# 2025-565-V1.net
KiCad netlist of a schematic drawn in Altium Designer
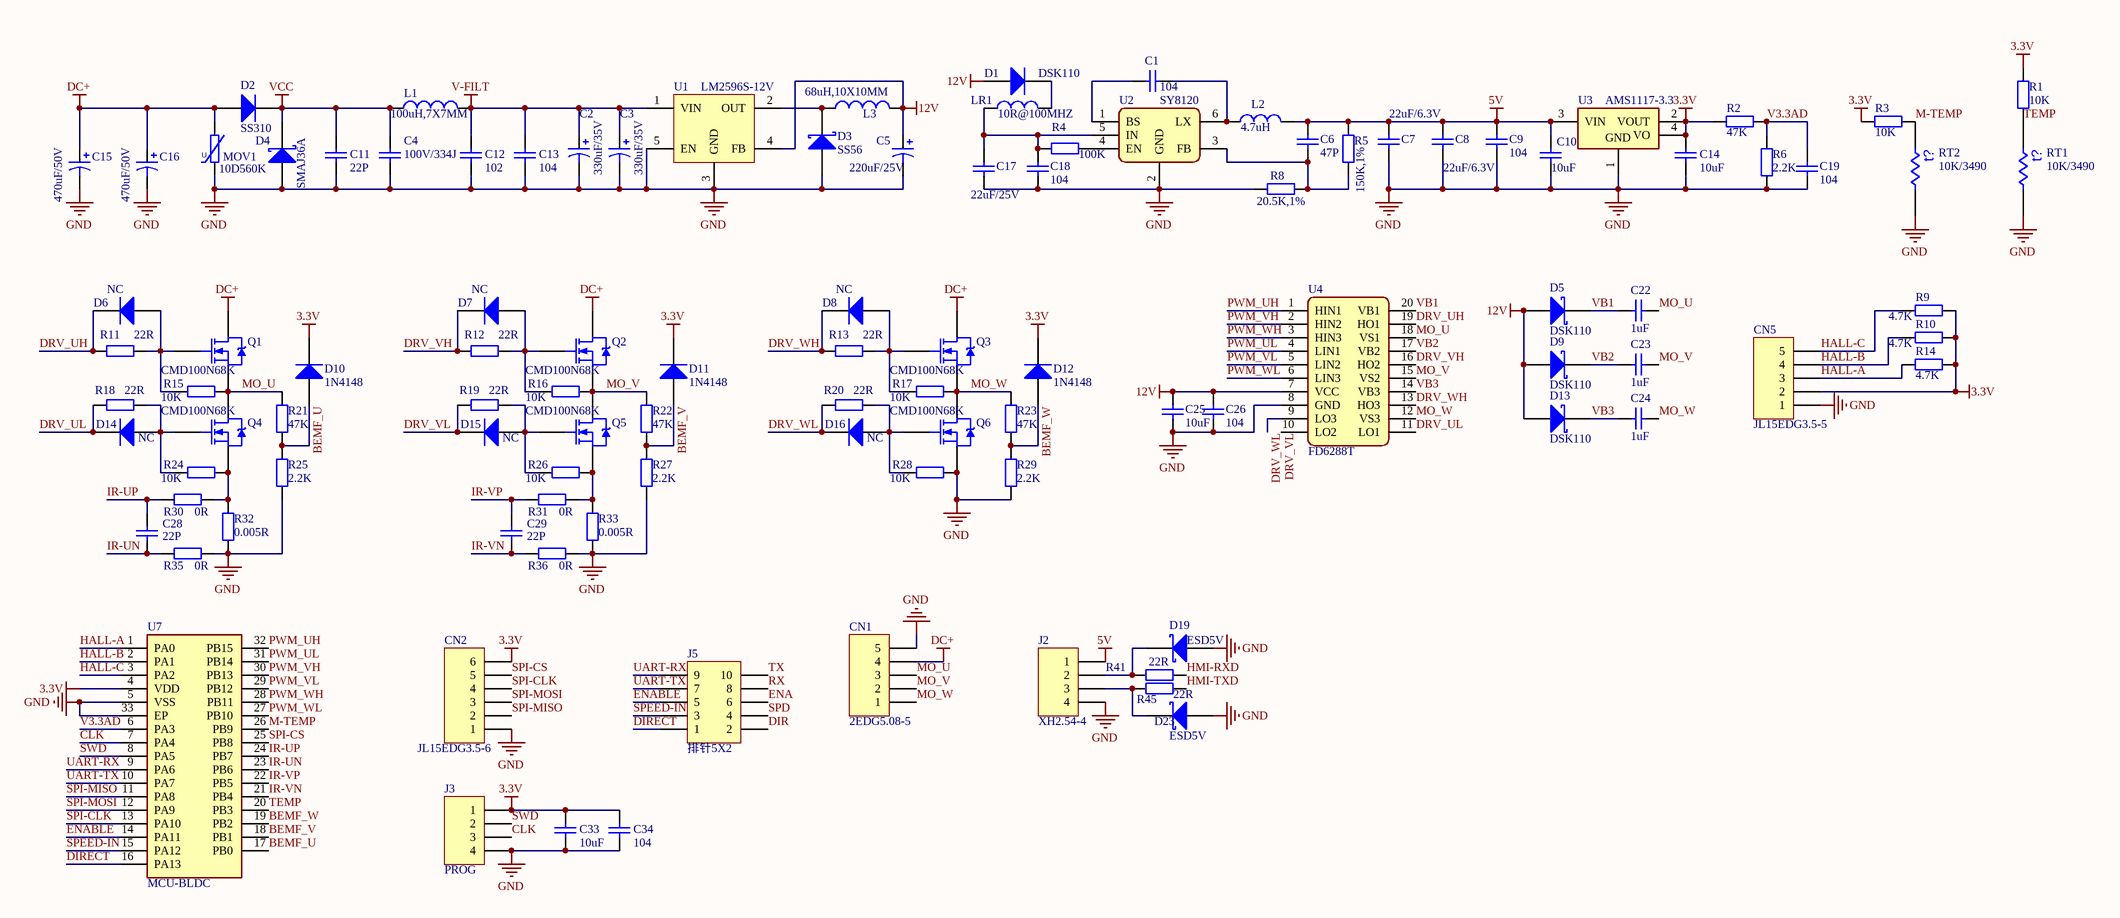
[diagram p0: 2025-565-V1.SchDoc]

(export (version "E")
  (design (tool "Eeschema 10.0.6"))
  (components
    (comp (ref "C1")
      (value "104")
      (footprint "0603-C")
      (description "0603电容")
      (fields (field (name "PUBLISHER") "Altium Limited"))
      (libsource (lib "Miscellaneous Devices") (part "Cap"))
    )
    (comp (ref "C2")
      (value "330uF/35V")
      (footprint "EC10-V5")
      (description "插件电解电容")
      (fields (field (name "PUBLISHER") "Altium Limited"))
      (libsource (lib "Miscellaneous Devices") (part "Cap Pol1"))
    )
    (comp (ref "C3")
      (value "330uF/35V")
      (footprint "EC10-V5")
      (description "插件电解电容")
      (fields (field (name "PUBLISHER") "Altium Limited"))
      (libsource (lib "Miscellaneous Devices") (part "Cap Pol1"))
    )
    (comp (ref "C4")
      (value "100V/334J")
      (footprint "CAP5-7.2X7.5X3.5")
      (description "校正电容")
      (fields (field (name "PUBLISHER") "Altium Limited"))
      (libsource (lib "Miscellaneous Devices") (part "Cap"))
    )
    (comp (ref "C5")
      (value "220uF/25V")
      (footprint "CAP_63*77")
      (description "贴片电解电容")
      (fields (field (name "PUBLISHER") "Altium Limited"))
      (libsource (lib "Miscellaneous Devices") (part "Cap Pol1"))
    )
    (comp (ref "C6")
      (value "47P")
      (footprint "0603-C")
      (description "0603电容")
      (fields (field (name "PUBLISHER") "Altium Limited"))
      (libsource (lib "Miscellaneous Devices") (part "Cap"))
    )
    (comp (ref "C7")
      (value "22uF/6.3V")
      (footprint "0603-C")
      (description "0603电容")
      (fields (field (name "PUBLISHER") "Altium Limited"))
      (libsource (lib "Miscellaneous Devices") (part "Cap"))
    )
    (comp (ref "C8")
      (value "22uF/6.3V")
      (footprint "0603-C")
      (description "0603电容")
      (fields (field (name "PUBLISHER") "Altium Limited"))
      (libsource (lib "Miscellaneous Devices") (part "Cap"))
    )
    (comp (ref "C9")
      (value "104")
      (footprint "0603-C")
      (description "0603电容")
      (fields (field (name "PUBLISHER") "Altium Limited"))
      (libsource (lib "Miscellaneous Devices") (part "Cap"))
    )
    (comp (ref "C10")
      (value "10uF")
      (footprint "0603-C")
      (description "0603电容")
      (fields (field (name "PUBLISHER") "Altium Limited"))
      (libsource (lib "Miscellaneous Devices") (part "Cap"))
    )
    (comp (ref "C11")
      (value "22P")
      (footprint "0603-C")
      (description "0603电容")
      (fields (field (name "PUBLISHER") "Altium Limited"))
      (libsource (lib "Miscellaneous Devices") (part "Cap"))
    )
    (comp (ref "C12")
      (value "102")
      (footprint "0603-C")
      (description "0603电容")
      (fields (field (name "PUBLISHER") "Altium Limited"))
      (libsource (lib "Miscellaneous Devices") (part "Cap"))
    )
    (comp (ref "C13")
      (value "104")
      (footprint "0603-C")
      (description "0603电容")
      (fields (field (name "PUBLISHER") "Altium Limited"))
      (libsource (lib "Miscellaneous Devices") (part "Cap"))
    )
    (comp (ref "C14")
      (value "10uF")
      (footprint "0603-C")
      (description "0603电容")
      (fields (field (name "PUBLISHER") "Altium Limited"))
      (libsource (lib "Miscellaneous Devices") (part "Cap"))
    )
    (comp (ref "C15")
      (value "470uF/50V")
      (footprint "EC10-V5")
      (description "插件电解电容")
      (fields (field (name "PUBLISHER") "Altium Limited"))
      (libsource (lib "Miscellaneous Devices") (part "Cap Pol1"))
    )
    (comp (ref "C16")
      (value "470uF/50V")
      (footprint "EC10-V5")
      (description "插件电解电容")
      (fields (field (name "PUBLISHER") "Altium Limited"))
      (libsource (lib "Miscellaneous Devices") (part "Cap Pol1"))
    )
    (comp (ref "C17")
      (value "22uF/25V")
      (footprint "1206-C")
      (description "1206电容")
      (fields (field (name "PUBLISHER") "Altium Limited"))
      (libsource (lib "Miscellaneous Devices") (part "Cap"))
    )
    (comp (ref "C18")
      (value "104")
      (footprint "0603-C")
      (description "0603电容")
      (fields (field (name "PUBLISHER") "Altium Limited"))
      (libsource (lib "Miscellaneous Devices") (part "Cap"))
    )
    (comp (ref "C19")
      (value "104")
      (footprint "0603-C")
      (description "0603电容")
      (fields (field (name "PUBLISHER") "Altium Limited"))
      (libsource (lib "Miscellaneous Devices") (part "Cap"))
    )
    (comp (ref "C22")
      (value "1uF")
      (footprint "0603-C")
      (description "0603电容")
      (fields (field (name "PUBLISHER") "Altium Limited"))
      (libsource (lib "Miscellaneous Devices") (part "Cap"))
    )
    (comp (ref "C23")
      (value "1uF")
      (footprint "0603-C")
      (description "0603电容")
      (fields (field (name "PUBLISHER") "Altium Limited"))
      (libsource (lib "Miscellaneous Devices") (part "Cap"))
    )
    (comp (ref "C24")
      (value "1uF")
      (footprint "0603-C")
      (description "0603电容")
      (fields (field (name "PUBLISHER") "Altium Limited"))
      (libsource (lib "Miscellaneous Devices") (part "Cap"))
    )
    (comp (ref "C25")
      (value "10uF")
      (footprint "1206-R")
      (description "1206电容")
      (fields (field (name "PUBLISHER") "Altium Limited"))
      (libsource (lib "Miscellaneous Devices") (part "Cap"))
    )
    (comp (ref "C26")
      (value "104")
      (footprint "0603-C")
      (description "0603电容")
      (fields (field (name "PUBLISHER") "Altium Limited"))
      (libsource (lib "Miscellaneous Devices") (part "Cap"))
    )
    (comp (ref "C28")
      (value "22P")
      (footprint "0603-C")
      (description "0603电容")
      (fields (field (name "PUBLISHER") "Altium Limited"))
      (libsource (lib "Miscellaneous Devices") (part "Cap"))
    )
    (comp (ref "C29")
      (value "22P")
      (footprint "0603-C")
      (description "0603电容")
      (fields (field (name "PUBLISHER") "Altium Limited"))
      (libsource (lib "Miscellaneous Devices") (part "Cap"))
    )
    (comp (ref "C33")
      (value "10uF")
      (footprint "0603-C")
      (description "0603电容")
      (fields (field (name "PUBLISHER") "Altium Limited"))
      (libsource (lib "Miscellaneous Devices") (part "Cap"))
    )
    (comp (ref "C34")
      (value "104")
      (footprint "0603-C")
      (description "0603电容")
      (fields (field (name "PUBLISHER") "Altium Limited"))
      (libsource (lib "Miscellaneous Devices") (part "Cap"))
    )
    (comp (ref "CN1")
      (value "2EDG5.08-5")
      (footprint "CON5_5.08MM_2EDG")
      (description "插拔端子")
      (fields (field (name "PUBLISHER") "Altium Limited"))
      (libsource (lib "Miscellaneous Connectors") (part "Header 5"))
    )
    (comp (ref "CN2")
      (value "JL15EDG3.5-6")
      (footprint "CON3.5*6-H-SPEC")
      (description "插拔端子")
      (fields (field (name "PUBLISHER") "Altium Limited"))
      (libsource (lib "Miscellaneous Connectors") (part "Header 6"))
    )
    (comp (ref "CN5")
      (value "JL15EDG3.5-5")
      (footprint "CON3.5*5-H-SPEC")
      (description "插拔端子")
      (fields (field (name "PUBLISHER") "Altium Limited"))
      (libsource (lib "Miscellaneous Connectors") (part "Header 5"))
    )
    (comp (ref "D1")
      (value "DSK110")
      (footprint "SOD-123FL")
      (description "二极管")
      (fields (field (name "PUBLISHER") "Altium Limited"))
      (libsource (lib "Miscellaneous Devices") (part "Diode"))
    )
    (comp (ref "D2")
      (value "SS310")
      (footprint "SMA-DO-214AC")
      (description "二极管")
      (fields (field (name "PUBLISHER") "Altium Limited"))
      (libsource (lib "Miscellaneous Devices") (part "Diode"))
    )
    (comp (ref "D3")
      (value "SS56")
      (footprint "SMB_DO-214AA")
      (description "肖特基二极管")
      (fields (field (name "PUBLISHER") "Altium Limited"))
      (libsource (lib "Miscellaneous Devices") (part "D Schottky"))
    )
    (comp (ref "D4")
      (value "SMAJ36A")
      (footprint "SMA-DO-214AC")
      (description "TVS二极管")
      (fields (field (name "PUBLISHER") "Altium Limited"))
      (libsource (lib "Miscellaneous Devices") (part "D Schottky"))
    )
    (comp (ref "D5")
      (value "DSK110")
      (footprint "SOD-123FL")
      (description "肖特基二极管")
      (fields (field (name "PUBLISHER") "Altium Limited"))
      (libsource (lib "Miscellaneous Devices") (part "D Schottky"))
    )
    (comp (ref "D6")
      (value "NC")
      (footprint "SOD-123")
      (description "Default Diode")
      (fields (field (name "PUBLISHER") "Altium Limited"))
      (libsource (lib "Miscellaneous Devices") (part "Diode"))
    )
    (comp (ref "D7")
      (value "NC")
      (footprint "SOD-123")
      (description "Default Diode")
      (fields (field (name "PUBLISHER") "Altium Limited"))
      (libsource (lib "Miscellaneous Devices") (part "Diode"))
    )
    (comp (ref "D8")
      (value "NC")
      (footprint "SOD-123")
      (description "Default Diode")
      (fields (field (name "PUBLISHER") "Altium Limited"))
      (libsource (lib "Miscellaneous Devices") (part "Diode"))
    )
    (comp (ref "D9")
      (value "DSK110")
      (footprint "SOD-123FL")
      (description "肖特基二极管")
      (fields (field (name "PUBLISHER") "Altium Limited"))
      (libsource (lib "Miscellaneous Devices") (part "D Schottky"))
    )
    (comp (ref "D10")
      (value "1N4148")
      (footprint "SOD-123")
      (description "Default Diode")
      (fields (field (name "PUBLISHER") "Altium Limited"))
      (libsource (lib "Miscellaneous Devices") (part "Diode"))
    )
    (comp (ref "D11")
      (value "1N4148")
      (footprint "SOD-123")
      (description "Default Diode")
      (fields (field (name "PUBLISHER") "Altium Limited"))
      (libsource (lib "Miscellaneous Devices") (part "Diode"))
    )
    (comp (ref "D12")
      (value "1N4148")
      (footprint "SOD-123")
      (description "Default Diode")
      (fields (field (name "PUBLISHER") "Altium Limited"))
      (libsource (lib "Miscellaneous Devices") (part "Diode"))
    )
    (comp (ref "D13")
      (value "DSK110")
      (footprint "SOD-123FL")
      (description "肖特基二极管")
      (fields (field (name "PUBLISHER") "Altium Limited"))
      (libsource (lib "Miscellaneous Devices") (part "D Schottky"))
    )
    (comp (ref "D14")
      (value "NC")
      (footprint "SOD-123")
      (description "Default Diode")
      (fields (field (name "PUBLISHER") "Altium Limited"))
      (libsource (lib "Miscellaneous Devices") (part "Diode"))
    )
    (comp (ref "D15")
      (value "NC")
      (footprint "SOD-123")
      (description "Default Diode")
      (fields (field (name "PUBLISHER") "Altium Limited"))
      (libsource (lib "Miscellaneous Devices") (part "Diode"))
    )
    (comp (ref "D16")
      (value "NC")
      (footprint "SOD-123")
      (description "Default Diode")
      (fields (field (name "PUBLISHER") "Altium Limited"))
      (libsource (lib "Miscellaneous Devices") (part "Diode"))
    )
    (comp (ref "D19")
      (value "ESD5V")
      (footprint "SOD-323")
      (description "TVS二极管")
      (fields (field (name "PUBLISHER") "Altium Limited"))
      (libsource (lib "Miscellaneous Devices") (part "D Schottky"))
    )
    (comp (ref "D23")
      (value "ESD5V")
      (footprint "SOD-323")
      (description "TVS二极管")
      (fields (field (name "PUBLISHER") "Altium Limited"))
      (libsource (lib "Miscellaneous Devices") (part "D Schottky"))
    )
    (comp (ref "J2")
      (value "XH2.54-4")
      (footprint "XH2.54_4")
      (description "XH连接器")
      (fields (field (name "PUBLISHER") "Altium Limited"))
      (libsource (lib "Miscellaneous Connectors") (part "Header 4"))
    )
    (comp (ref "J3")
      (value "PROG")
      (footprint "HDR1X4")
      (description "NC")
      (fields (field (name "PUBLISHER") "Altium Limited"))
      (libsource (lib "Miscellaneous Connectors") (part "Header 4"))
    )
    (comp (ref "J5")
      (value "排针5X2")
      (footprint "HDR2X5")
      (description "排针")
      (fields (field (name "PUBLISHER") "Altium Limited"))
      (libsource (lib "Miscellaneous Connectors") (part "Header 5X2"))
    )
    (comp (ref "L1")
      (value "100uH,7X7MM")
      (footprint "L-7X7-2")
      (description "贴片电感")
      (fields (field (name "PUBLISHER") "Altium Limited"))
      (libsource (lib "Miscellaneous Devices") (part "Inductor"))
    )
    (comp (ref "L2")
      (value "4.7uH")
      (footprint "L-0420")
      (description "一体成型电感")
      (libsource (lib "general device") (part "L"))
    )
    (comp (ref "L3")
      (value "68uH,10X10MM")
      (footprint "L-1050")
      (description "贴片功率电感")
      (fields (field (name "PUBLISHER") "Altium Limited"))
      (libsource (lib "Miscellaneous Devices") (part "Inductor"))
    )
    (comp (ref "LR1")
      (value "10R@100MHZ")
      (footprint "0603-R")
      (description "0603磁珠")
      (libsource (lib "general device") (part "L"))
    )
    (comp (ref "MOV1")
      (value "10D560K")
      (footprint "RES-VAR-10D")
      (description "压敏电阻")
      (libsource (lib "general device") (part "RES-VAR"))
    )
    (comp (ref "Q1")
      (value "CMD100N68K")
      (footprint "TO-252")
      (description "N-Channel Power MOSFET")
      (fields (field (name "PUBLISHER") "Altium Limited"))
      (libsource (lib "Miscellaneous Devices") (part "NMOS-2"))
    )
    (comp (ref "Q2")
      (value "CMD100N68K")
      (footprint "TO-252")
      (description "N-Channel Power MOSFET")
      (fields (field (name "PUBLISHER") "Altium Limited"))
      (libsource (lib "Miscellaneous Devices") (part "NMOS-2"))
    )
    (comp (ref "Q3")
      (value "CMD100N68K")
      (footprint "TO-252")
      (description "N-Channel Power MOSFET")
      (fields (field (name "PUBLISHER") "Altium Limited"))
      (libsource (lib "Miscellaneous Devices") (part "NMOS-2"))
    )
    (comp (ref "Q4")
      (value "CMD100N68K")
      (footprint "TO-252")
      (description "N-Channel Power MOSFET")
      (fields (field (name "PUBLISHER") "Altium Limited"))
      (libsource (lib "Miscellaneous Devices") (part "NMOS-2"))
    )
    (comp (ref "Q5")
      (value "CMD100N68K")
      (footprint "TO-252")
      (description "N-Channel Power MOSFET")
      (fields (field (name "PUBLISHER") "Altium Limited"))
      (libsource (lib "Miscellaneous Devices") (part "NMOS-2"))
    )
    (comp (ref "Q6")
      (value "CMD100N68K")
      (footprint "TO-252")
      (description "N-Channel Power MOSFET")
      (fields (field (name "PUBLISHER") "Altium Limited"))
      (libsource (lib "Miscellaneous Devices") (part "NMOS-2"))
    )
    (comp (ref "R1")
      (value "10K")
      (footprint "0603-R")
      (description "0603电阻")
      (fields (field (name "PUBLISHER") "Altium Limited"))
      (libsource (lib "") (part "Res2_2"))
    )
    (comp (ref "R2")
      (value "47K")
      (footprint "0603-R")
      (description "0603电阻")
      (fields (field (name "PUBLISHER") "Altium Limited"))
      (libsource (lib "") (part "Res2_1"))
    )
    (comp (ref "R3")
      (value "10K")
      (footprint "0603-R")
      (description "0603电阻")
      (fields (field (name "PUBLISHER") "Altium Limited"))
      (libsource (lib "") (part "Res2_1"))
    )
    (comp (ref "R4")
      (value "100K")
      (footprint "0603-R")
      (description "0603电阻")
      (fields (field (name "PUBLISHER") "Altium Limited"))
      (libsource (lib "Miscellaneous Devices") (part "Res2"))
    )
    (comp (ref "R5")
      (value "150K,1%")
      (footprint "0603-R")
      (description "0603电阻")
      (fields (field (name "PUBLISHER") "Altium Limited"))
      (libsource (lib "") (part "Res2_2"))
    )
    (comp (ref "R6")
      (value "2.2K")
      (footprint "0603-R")
      (description "0603电阻")
      (fields (field (name "PUBLISHER") "Altium Limited"))
      (libsource (lib "") (part "Res2_3"))
    )
    (comp (ref "R8")
      (value "20.5K,1%")
      (footprint "0603-R")
      (description "0603电阻")
      (fields (field (name "PUBLISHER") "Altium Limited"))
      (libsource (lib "Miscellaneous Devices") (part "Res2"))
    )
    (comp (ref "R9")
      (value "4.7K")
      (footprint "0603-R")
      (description "0603电阻")
      (fields (field (name "PUBLISHER") "Altium Limited"))
      (libsource (lib "") (part "Res2_1"))
    )
    (comp (ref "R10")
      (value "4.7K")
      (footprint "0603-R")
      (description "0603电阻")
      (fields (field (name "PUBLISHER") "Altium Limited"))
      (libsource (lib "") (part "Res2_1"))
    )
    (comp (ref "R11")
      (value "22R")
      (footprint "0603-R")
      (description "0603电阻")
      (fields (field (name "PUBLISHER") "Altium Limited"))
      (libsource (lib "Miscellaneous Devices") (part "Res2"))
    )
    (comp (ref "R12")
      (value "22R")
      (footprint "0603-R")
      (description "0603电阻")
      (fields (field (name "PUBLISHER") "Altium Limited"))
      (libsource (lib "Miscellaneous Devices") (part "Res2"))
    )
    (comp (ref "R13")
      (value "22R")
      (footprint "0603-R")
      (description "0603电阻")
      (fields (field (name "PUBLISHER") "Altium Limited"))
      (libsource (lib "Miscellaneous Devices") (part "Res2"))
    )
    (comp (ref "R14")
      (value "4.7K")
      (footprint "0603-R")
      (description "0603电阻")
      (fields (field (name "PUBLISHER") "Altium Limited"))
      (libsource (lib "") (part "Res2_1"))
    )
    (comp (ref "R15")
      (value "10K")
      (footprint "0603-R")
      (description "0603电阻")
      (fields (field (name "PUBLISHER") "Altium Limited"))
      (libsource (lib "Miscellaneous Devices") (part "Res2"))
    )
    (comp (ref "R16")
      (value "10K")
      (footprint "0603-R")
      (description "0603电阻")
      (fields (field (name "PUBLISHER") "Altium Limited"))
      (libsource (lib "Miscellaneous Devices") (part "Res2"))
    )
    (comp (ref "R17")
      (value "10K")
      (footprint "0603-R")
      (description "0603电阻")
      (fields (field (name "PUBLISHER") "Altium Limited"))
      (libsource (lib "Miscellaneous Devices") (part "Res2"))
    )
    (comp (ref "R18")
      (value "22R")
      (footprint "0603-R")
      (description "0603电阻")
      (fields (field (name "PUBLISHER") "Altium Limited"))
      (libsource (lib "Miscellaneous Devices") (part "Res2"))
    )
    (comp (ref "R19")
      (value "22R")
      (footprint "0603-R")
      (description "0603电阻")
      (fields (field (name "PUBLISHER") "Altium Limited"))
      (libsource (lib "Miscellaneous Devices") (part "Res2"))
    )
    (comp (ref "R20")
      (value "22R")
      (footprint "0603-R")
      (description "0603电阻")
      (fields (field (name "PUBLISHER") "Altium Limited"))
      (libsource (lib "Miscellaneous Devices") (part "Res2"))
    )
    (comp (ref "R21")
      (value "47K")
      (footprint "0603-R")
      (description "0603电阻")
      (fields (field (name "PUBLISHER") "Altium Limited"))
      (libsource (lib "") (part "Res2_2"))
    )
    (comp (ref "R22")
      (value "47K")
      (footprint "0603-R")
      (description "0603电阻")
      (fields (field (name "PUBLISHER") "Altium Limited"))
      (libsource (lib "") (part "Res2_2"))
    )
    (comp (ref "R23")
      (value "47K")
      (footprint "0603-R")
      (description "0603电阻")
      (fields (field (name "PUBLISHER") "Altium Limited"))
      (libsource (lib "") (part "Res2_2"))
    )
    (comp (ref "R24")
      (value "10K")
      (footprint "0603-R")
      (description "0603电阻")
      (fields (field (name "PUBLISHER") "Altium Limited"))
      (libsource (lib "Miscellaneous Devices") (part "Res2"))
    )
    (comp (ref "R25")
      (value "2.2K")
      (footprint "0603-R")
      (description "0603电阻")
      (fields (field (name "PUBLISHER") "Altium Limited"))
      (libsource (lib "") (part "Res2_2"))
    )
    (comp (ref "R26")
      (value "10K")
      (footprint "0603-R")
      (description "0603电阻")
      (fields (field (name "PUBLISHER") "Altium Limited"))
      (libsource (lib "Miscellaneous Devices") (part "Res2"))
    )
    (comp (ref "R27")
      (value "2.2K")
      (footprint "0603-R")
      (description "0603电阻")
      (fields (field (name "PUBLISHER") "Altium Limited"))
      (libsource (lib "") (part "Res2_2"))
    )
    (comp (ref "R28")
      (value "10K")
      (footprint "0603-R")
      (description "0603电阻")
      (fields (field (name "PUBLISHER") "Altium Limited"))
      (libsource (lib "Miscellaneous Devices") (part "Res2"))
    )
    (comp (ref "R29")
      (value "2.2K")
      (footprint "0603-R")
      (description "0603电阻")
      (fields (field (name "PUBLISHER") "Altium Limited"))
      (libsource (lib "") (part "Res2_2"))
    )
    (comp (ref "R30")
      (value "0R")
      (footprint "0603-R")
      (description "0603电阻")
      (fields (field (name "PUBLISHER") "Altium Limited"))
      (libsource (lib "") (part "Res2_1"))
    )
    (comp (ref "R31")
      (value "0R")
      (footprint "0603-R")
      (description "0603电阻")
      (fields (field (name "PUBLISHER") "Altium Limited"))
      (libsource (lib "") (part "Res2_1"))
    )
    (comp (ref "R32")
      (value "0.005R")
      (footprint "RES2512")
      (description "2512合金电阻")
      (fields (field (name "PUBLISHER") "Altium Limited"))
      (libsource (lib "") (part "Res2_2"))
    )
    (comp (ref "R33")
      (value "0.005R")
      (footprint "RES2512")
      (description "2512合金电阻")
      (fields (field (name "PUBLISHER") "Altium Limited"))
      (libsource (lib "") (part "Res2_2"))
    )
    (comp (ref "R35")
      (value "0R")
      (footprint "0603-R")
      (description "0603电阻")
      (fields (field (name "PUBLISHER") "Altium Limited"))
      (libsource (lib "") (part "Res2_1"))
    )
    (comp (ref "R36")
      (value "0R")
      (footprint "0603-R")
      (description "0603电阻")
      (fields (field (name "PUBLISHER") "Altium Limited"))
      (libsource (lib "") (part "Res2_1"))
    )
    (comp (ref "R41")
      (value "22R")
      (footprint "0603-R")
      (description "0603电阻")
      (fields (field (name "PUBLISHER") "Altium Limited"))
      (libsource (lib "") (part "Res2_1"))
    )
    (comp (ref "R45")
      (value "22R")
      (footprint "0603-R")
      (description "0603电阻")
      (fields (field (name "PUBLISHER") "Altium Limited"))
      (libsource (lib "") (part "Res2_1"))
    )
    (comp (ref "RT1")
      (value "10K/3490")
      (footprint "0603-R")
      (description "热敏电阻")
      (fields (field (name "PUBLISHER") "Altium Limited"))
      (libsource (lib "Miscellaneous Devices") (part "Res Thermal"))
    )
    (comp (ref "RT2")
      (value "10K/3490")
      (footprint "PAD0.7X2")
      (description "热敏电阻")
      (fields (field (name "PUBLISHER") "Altium Limited"))
      (libsource (lib "Miscellaneous Devices") (part "Res Thermal"))
    )
    (comp (ref "U1")
      (value "LM2596S-12V")
      (footprint "TO-263-5")
      (description "DC-DC降压芯片")
      (libsource (lib "general device") (part "LM2596"))
    )
    (comp (ref "U2")
      (value "SY8120")
      (footprint "SOT23-6")
      (description "DC-DC降压芯片")
      (libsource (lib "general device") (part "SY8120"))
    )
    (comp (ref "U3")
      (value "AMS1117-3.3")
      (footprint "SOT-223")
      (description "LDO稳压器")
      (libsource (lib "general device") (part "AMS1117"))
    )
    (comp (ref "U4")
      (value "FD6288T")
      (footprint "TSSOP20")
      (description "全桥栅极驱动器")
      (libsource (lib "general device") (part "FD6288T"))
    )
    (comp (ref "U7")
      (value "MCU-BLDC")
      (footprint "QFN32-EP-5X5")
      (description "MCU")
      (libsource (lib "general device") (part "MCU-BLDC"))
    )
  )
  (nets
    (net (code "1") (name "/BEMF_U") (class "Default")
      (node (ref "D10") (pin "1") (pinfunction "A_1") (pintype "passive"))
      (node (ref "R21") (pin "1") (pinfunction "1_1") (pintype "passive"))
      (node (ref "R25") (pin "2") (pinfunction "2_2") (pintype "passive"))
      (node (ref "U7") (pin "17") (pinfunction "PB0_17") (pintype "passive"))
    )
    (net (code "2") (name "/BEMF_V") (class "Default")
      (node (ref "D11") (pin "1") (pinfunction "A_1") (pintype "passive"))
      (node (ref "R22") (pin "1") (pinfunction "1_1") (pintype "passive"))
      (node (ref "R27") (pin "2") (pinfunction "2_2") (pintype "passive"))
      (node (ref "U7") (pin "18") (pinfunction "PB1_18") (pintype "passive"))
    )
    (net (code "3") (name "/BEMF_W") (class "Default")
      (node (ref "D12") (pin "1") (pinfunction "A_1") (pintype "passive"))
      (node (ref "R23") (pin "1") (pinfunction "1_1") (pintype "passive"))
      (node (ref "R29") (pin "2") (pinfunction "2_2") (pintype "passive"))
      (node (ref "U7") (pin "19") (pinfunction "PB2_19") (pintype "passive"))
    )
    (net (code "4") (name "/CLK") (class "Default")
      (node (ref "J3") (pin "3") (pinfunction "3_3") (pintype "passive"))
      (node (ref "U7") (pin "7") (pinfunction "PA4_7") (pintype "passive"))
    )
    (net (code "5") (name "/DIR") (class "Default")
      (node (ref "J5") (pin "2") (pinfunction "2_2") (pintype "passive"))
    )
    (net (code "6") (name "/DIRECT") (class "Default")
      (node (ref "J5") (pin "1") (pinfunction "1_1") (pintype "passive"))
      (node (ref "U7") (pin "16") (pinfunction "PA13_16") (pintype "passive"))
    )
    (net (code "7") (name "/DRV_UH") (class "Default")
      (node (ref "D6") (pin "2") (pinfunction "K_2") (pintype "passive"))
      (node (ref "R11") (pin "1") (pinfunction "1_1") (pintype "passive"))
      (node (ref "U4") (pin "19") (pinfunction "HO1_19") (pintype "passive"))
    )
    (net (code "8") (name "/DRV_UL") (class "Default")
      (node (ref "D14") (pin "2") (pinfunction "K_2") (pintype "passive"))
      (node (ref "R18") (pin "1") (pinfunction "1_1") (pintype "passive"))
      (node (ref "U4") (pin "11") (pinfunction "LO1_11") (pintype "passive"))
    )
    (net (code "9") (name "/DRV_VH") (class "Default")
      (node (ref "D7") (pin "2") (pinfunction "K_2") (pintype "passive"))
      (node (ref "R12") (pin "1") (pinfunction "1_1") (pintype "passive"))
      (node (ref "U4") (pin "16") (pinfunction "HO2_16") (pintype "passive"))
    )
    (net (code "10") (name "/DRV_VL") (class "Default")
      (node (ref "D15") (pin "2") (pinfunction "K_2") (pintype "passive"))
      (node (ref "R19") (pin "1") (pinfunction "1_1") (pintype "passive"))
      (node (ref "U4") (pin "10") (pinfunction "LO2_10") (pintype "passive"))
    )
    (net (code "11") (name "/DRV_WH") (class "Default")
      (node (ref "D8") (pin "2") (pinfunction "K_2") (pintype "passive"))
      (node (ref "R13") (pin "1") (pinfunction "1_1") (pintype "passive"))
      (node (ref "U4") (pin "13") (pinfunction "HO3_13") (pintype "passive"))
    )
    (net (code "12") (name "/DRV_WL") (class "Default")
      (node (ref "D16") (pin "2") (pinfunction "K_2") (pintype "passive"))
      (node (ref "R20") (pin "1") (pinfunction "1_1") (pintype "passive"))
      (node (ref "U4") (pin "9") (pinfunction "LO3_9") (pintype "passive"))
    )
    (net (code "13") (name "/ENA") (class "Default")
      (node (ref "J5") (pin "6") (pinfunction "6_6") (pintype "passive"))
    )
    (net (code "14") (name "/ENABLE") (class "Default")
      (node (ref "J5") (pin "5") (pinfunction "5_5") (pintype "passive"))
      (node (ref "U7") (pin "14") (pinfunction "PA11_14") (pintype "passive"))
    )
    (net (code "15") (name "/HALL-A") (class "Default")
      (node (ref "CN5") (pin "3") (pinfunction "3_3") (pintype "passive"))
      (node (ref "R14") (pin "2") (pinfunction "2_2") (pintype "passive"))
      (node (ref "U7") (pin "1") (pinfunction "PA0_1") (pintype "passive"))
    )
    (net (code "16") (name "/HALL-B") (class "Default")
      (node (ref "CN5") (pin "4") (pinfunction "4_4") (pintype "passive"))
      (node (ref "R10") (pin "2") (pinfunction "2_2") (pintype "passive"))
      (node (ref "U7") (pin "2") (pinfunction "PA1_2") (pintype "passive"))
    )
    (net (code "17") (name "/HALL-C") (class "Default")
      (node (ref "CN5") (pin "5") (pinfunction "5_5") (pintype "passive"))
      (node (ref "R9") (pin "2") (pinfunction "2_2") (pintype "passive"))
      (node (ref "U7") (pin "3") (pinfunction "PA2_3") (pintype "passive"))
    )
    (net (code "18") (name "/HMI-RXD") (class "Default")
      (node (ref "R41") (pin "1") (pinfunction "1_1") (pintype "passive"))
    )
    (net (code "19") (name "/HMI-TXD") (class "Default")
      (node (ref "R45") (pin "1") (pinfunction "1_1") (pintype "passive"))
    )
    (net (code "20") (name "/IR-UN") (class "Default")
      (node (ref "C28") (pin "1") (pinfunction "1_1") (pintype "passive"))
      (node (ref "R35") (pin "2") (pinfunction "2_2") (pintype "passive"))
      (node (ref "U7") (pin "23") (pinfunction "PB6_23") (pintype "passive"))
    )
    (net (code "21") (name "/IR-UP") (class "Default")
      (node (ref "C28") (pin "2") (pinfunction "2_2") (pintype "passive"))
      (node (ref "R30") (pin "2") (pinfunction "2_2") (pintype "passive"))
      (node (ref "U7") (pin "24") (pinfunction "PB7_24") (pintype "passive"))
    )
    (net (code "22") (name "/IR-VN") (class "Default")
      (node (ref "C29") (pin "1") (pinfunction "1_1") (pintype "passive"))
      (node (ref "R36") (pin "2") (pinfunction "2_2") (pintype "passive"))
      (node (ref "U7") (pin "21") (pinfunction "PB4_21") (pintype "passive"))
    )
    (net (code "23") (name "/IR-VP") (class "Default")
      (node (ref "C29") (pin "2") (pinfunction "2_2") (pintype "passive"))
      (node (ref "R31") (pin "2") (pinfunction "2_2") (pintype "passive"))
      (node (ref "U7") (pin "22") (pinfunction "PB5_22") (pintype "passive"))
    )
    (net (code "24") (name "/M-TEMP") (class "Default")
      (node (ref "R3") (pin "1") (pinfunction "1_1") (pintype "passive"))
      (node (ref "RT2") (pin "1") (pinfunction "1_1") (pintype "passive"))
      (node (ref "U7") (pin "26") (pinfunction "PB9_26") (pintype "passive"))
    )
    (net (code "25") (name "/MO_U") (class "Default")
      (node (ref "C22") (pin "1") (pinfunction "1_1") (pintype "passive"))
      (node (ref "CN1") (pin "3") (pinfunction "3_3") (pintype "passive"))
      (node (ref "Q1") (pin "3") (pinfunction "S_3") (pintype "passive"))
      (node (ref "Q4") (pin "2") (pinfunction "D_2") (pintype "passive"))
      (node (ref "R15") (pin "2") (pinfunction "2_2") (pintype "passive"))
      (node (ref "R21") (pin "2") (pinfunction "2_2") (pintype "passive"))
      (node (ref "U4") (pin "18") (pinfunction "VS1_18") (pintype "passive"))
    )
    (net (code "26") (name "/MO_V") (class "Default")
      (node (ref "C23") (pin "1") (pinfunction "1_1") (pintype "passive"))
      (node (ref "CN1") (pin "2") (pinfunction "2_2") (pintype "passive"))
      (node (ref "Q2") (pin "3") (pinfunction "S_3") (pintype "passive"))
      (node (ref "Q5") (pin "2") (pinfunction "D_2") (pintype "passive"))
      (node (ref "R16") (pin "2") (pinfunction "2_2") (pintype "passive"))
      (node (ref "R22") (pin "2") (pinfunction "2_2") (pintype "passive"))
      (node (ref "U4") (pin "15") (pinfunction "VS2_15") (pintype "passive"))
    )
    (net (code "27") (name "/MO_W") (class "Default")
      (node (ref "C24") (pin "1") (pinfunction "1_1") (pintype "passive"))
      (node (ref "CN1") (pin "1") (pinfunction "1_1") (pintype "passive"))
      (node (ref "Q3") (pin "3") (pinfunction "S_3") (pintype "passive"))
      (node (ref "Q6") (pin "2") (pinfunction "D_2") (pintype "passive"))
      (node (ref "R17") (pin "2") (pinfunction "2_2") (pintype "passive"))
      (node (ref "R23") (pin "2") (pinfunction "2_2") (pintype "passive"))
      (node (ref "U4") (pin "12") (pinfunction "VS3_12") (pintype "passive"))
    )
    (net (code "28") (name "/PWM_UH") (class "Default")
      (node (ref "U4") (pin "1") (pinfunction "HIN1_1") (pintype "passive"))
      (node (ref "U7") (pin "32") (pinfunction "PB15_32") (pintype "passive"))
    )
    (net (code "29") (name "/PWM_UL") (class "Default")
      (node (ref "U4") (pin "4") (pinfunction "LIN1_4") (pintype "passive"))
      (node (ref "U7") (pin "31") (pinfunction "PB14_31") (pintype "passive"))
    )
    (net (code "30") (name "/PWM_VH") (class "Default")
      (node (ref "U4") (pin "2") (pinfunction "HIN2_2") (pintype "passive"))
      (node (ref "U7") (pin "30") (pinfunction "PB13_30") (pintype "passive"))
    )
    (net (code "31") (name "/PWM_VL") (class "Default")
      (node (ref "U4") (pin "5") (pinfunction "LIN2_5") (pintype "passive"))
      (node (ref "U7") (pin "29") (pinfunction "PB12_29") (pintype "passive"))
    )
    (net (code "32") (name "/PWM_WH") (class "Default")
      (node (ref "U4") (pin "3") (pinfunction "HIN3_3") (pintype "passive"))
      (node (ref "U7") (pin "28") (pinfunction "PB11_28") (pintype "passive"))
    )
    (net (code "33") (name "/PWM_WL") (class "Default")
      (node (ref "U4") (pin "6") (pinfunction "LIN3_6") (pintype "passive"))
      (node (ref "U7") (pin "27") (pinfunction "PB10_27") (pintype "passive"))
    )
    (net (code "34") (name "/RX") (class "Default")
      (node (ref "J5") (pin "8") (pinfunction "8_8") (pintype "passive"))
    )
    (net (code "35") (name "/SPD") (class "Default")
      (node (ref "J5") (pin "4") (pinfunction "4_4") (pintype "passive"))
    )
    (net (code "36") (name "/SPEED-IN") (class "Default")
      (node (ref "J5") (pin "3") (pinfunction "3_3") (pintype "passive"))
      (node (ref "U7") (pin "15") (pinfunction "PA12_15") (pintype "passive"))
    )
    (net (code "37") (name "/SPI-CLK") (class "Default")
      (node (ref "CN2") (pin "4") (pinfunction "4_4") (pintype "passive"))
      (node (ref "U7") (pin "13") (pinfunction "PA10_13") (pintype "passive"))
    )
    (net (code "38") (name "/SPI-CS") (class "Default")
      (node (ref "CN2") (pin "5") (pinfunction "5_5") (pintype "passive"))
      (node (ref "U7") (pin "25") (pinfunction "PB8_25") (pintype "passive"))
    )
    (net (code "39") (name "/SPI-MISO") (class "Default")
      (node (ref "CN2") (pin "2") (pinfunction "2_2") (pintype "passive"))
      (node (ref "U7") (pin "11") (pinfunction "PA8_11") (pintype "passive"))
    )
    (net (code "40") (name "/SPI-MOSI") (class "Default")
      (node (ref "CN2") (pin "3") (pinfunction "3_3") (pintype "passive"))
      (node (ref "U7") (pin "12") (pinfunction "PA9_12") (pintype "passive"))
    )
    (net (code "41") (name "/SWD") (class "Default")
      (node (ref "J3") (pin "2") (pinfunction "2_2") (pintype "passive"))
      (node (ref "U7") (pin "8") (pinfunction "PA5_8") (pintype "passive"))
    )
    (net (code "42") (name "/TEMP") (class "Default")
      (node (ref "R1") (pin "1") (pinfunction "1_1") (pintype "passive"))
      (node (ref "RT1") (pin "1") (pinfunction "1_1") (pintype "passive"))
      (node (ref "U7") (pin "20") (pinfunction "PB3_20") (pintype "passive"))
    )
    (net (code "43") (name "/TX") (class "Default")
      (node (ref "J5") (pin "10") (pinfunction "10_10") (pintype "passive"))
    )
    (net (code "44") (name "/UART-RX") (class "Default")
      (node (ref "J5") (pin "9") (pinfunction "9_9") (pintype "passive"))
      (node (ref "U7") (pin "9") (pinfunction "PA6_9") (pintype "passive"))
    )
    (net (code "45") (name "/UART-TX") (class "Default")
      (node (ref "J5") (pin "7") (pinfunction "7_7") (pintype "passive"))
      (node (ref "U7") (pin "10") (pinfunction "PA7_10") (pintype "passive"))
    )
    (net (code "46") (name "/V3.3AD") (class "Default")
      (node (ref "C19") (pin "2") (pinfunction "2_2") (pintype "passive"))
      (node (ref "R2") (pin "1") (pinfunction "1_1") (pintype "passive"))
      (node (ref "R6") (pin "1") (pinfunction "1_1") (pintype "passive"))
      (node (ref "U7") (pin "6") (pinfunction "PA3_6") (pintype "passive"))
    )
    (net (code "47") (name "/VB1") (class "Default")
      (node (ref "C22") (pin "2") (pinfunction "2_2") (pintype "passive"))
      (node (ref "D5") (pin "2") (pinfunction "K_2") (pintype "passive"))
      (node (ref "U4") (pin "20") (pinfunction "VB1_20") (pintype "passive"))
    )
    (net (code "48") (name "/VB2") (class "Default")
      (node (ref "C23") (pin "2") (pinfunction "2_2") (pintype "passive"))
      (node (ref "D9") (pin "2") (pinfunction "K_2") (pintype "passive"))
      (node (ref "U4") (pin "17") (pinfunction "VB2_17") (pintype "passive"))
    )
    (net (code "49") (name "/VB3") (class "Default")
      (node (ref "C24") (pin "2") (pinfunction "2_2") (pintype "passive"))
      (node (ref "D13") (pin "2") (pinfunction "K_2") (pintype "passive"))
      (node (ref "U4") (pin "14") (pinfunction "VB3_14") (pintype "passive"))
    )
    (net (code "50") (name "3.3V") (class "Default")
      (node (ref "C14") (pin "2") (pinfunction "2_2") (pintype "passive"))
      (node (ref "C33") (pin "2") (pinfunction "2_2") (pintype "passive"))
      (node (ref "C34") (pin "2") (pinfunction "2_2") (pintype "passive"))
      (node (ref "CN2") (pin "6") (pinfunction "6_6") (pintype "passive"))
      (node (ref "CN5") (pin "2") (pinfunction "2_2") (pintype "passive"))
      (node (ref "D10") (pin "2") (pinfunction "K_2") (pintype "passive"))
      (node (ref "D11") (pin "2") (pinfunction "K_2") (pintype "passive"))
      (node (ref "D12") (pin "2") (pinfunction "K_2") (pintype "passive"))
      (node (ref "J3") (pin "1") (pinfunction "1_1") (pintype "passive"))
      (node (ref "R1") (pin "2") (pinfunction "2_2") (pintype "passive"))
      (node (ref "R10") (pin "1") (pinfunction "1_1") (pintype "passive"))
      (node (ref "R14") (pin "1") (pinfunction "1_1") (pintype "passive"))
      (node (ref "R2") (pin "2") (pinfunction "2_2") (pintype "passive"))
      (node (ref "R3") (pin "2") (pinfunction "2_2") (pintype "passive"))
      (node (ref "R9") (pin "1") (pinfunction "1_1") (pintype "passive"))
      (node (ref "U3") (pin "2") (pinfunction "VOUT_2") (pintype "passive"))
      (node (ref "U3") (pin "4") (pinfunction "VO_4") (pintype "passive"))
      (node (ref "U7") (pin "4") (pinfunction "VDD_4") (pintype "passive"))
    )
    (net (code "51") (name "5V") (class "Default")
      (node (ref "C10") (pin "2") (pinfunction "2_2") (pintype "passive"))
      (node (ref "C6") (pin "2") (pinfunction "2_2") (pintype "passive"))
      (node (ref "C7") (pin "2") (pinfunction "2_2") (pintype "passive"))
      (node (ref "C8") (pin "2") (pinfunction "2_2") (pintype "passive"))
      (node (ref "C9") (pin "2") (pinfunction "2_2") (pintype "passive"))
      (node (ref "J2") (pin "1") (pinfunction "1_1") (pintype "passive"))
      (node (ref "L2") (pin "2") (pinfunction "2_2") (pintype "passive"))
      (node (ref "R5") (pin "2") (pinfunction "2_2") (pintype "passive"))
      (node (ref "U3") (pin "3") (pinfunction "VIN_3") (pintype "passive"))
    )
    (net (code "52") (name "12V") (class "Default")
      (node (ref "C25") (pin "1") (pinfunction "1_1") (pintype "passive"))
      (node (ref "C26") (pin "1") (pinfunction "1_1") (pintype "passive"))
      (node (ref "C5") (pin "1") (pinfunction "1_1") (pintype "passive"))
      (node (ref "D1") (pin "1") (pinfunction "A_1") (pintype "passive"))
      (node (ref "D13") (pin "1") (pinfunction "A_1") (pintype "passive"))
      (node (ref "D5") (pin "1") (pinfunction "A_1") (pintype "passive"))
      (node (ref "D9") (pin "1") (pinfunction "A_1") (pintype "passive"))
      (node (ref "L3") (pin "2") (pinfunction "2_2") (pintype "passive"))
      (node (ref "U1") (pin "4") (pinfunction "FB_4") (pintype "passive"))
      (node (ref "U4") (pin "7") (pinfunction "VCC_7") (pintype "passive"))
    )
    (net (code "53") (name "DC+") (class "Default")
      (node (ref "C15") (pin "1") (pinfunction "1_1") (pintype "passive"))
      (node (ref "C16") (pin "1") (pinfunction "1_1") (pintype "passive"))
      (node (ref "CN1") (pin "4") (pinfunction "4_4") (pintype "passive"))
      (node (ref "D2") (pin "1") (pinfunction "A_1") (pintype "passive"))
      (node (ref "MOV1") (pin "1") (pinfunction "1_1") (pintype "passive"))
      (node (ref "Q1") (pin "2") (pinfunction "D_2") (pintype "passive"))
      (node (ref "Q2") (pin "2") (pinfunction "D_2") (pintype "passive"))
      (node (ref "Q3") (pin "2") (pinfunction "D_2") (pintype "passive"))
    )
    (net (code "54") (name "GND") (class "Default")
      (node (ref "C10") (pin "1") (pinfunction "1_1") (pintype "passive"))
      (node (ref "C11") (pin "1") (pinfunction "1_1") (pintype "passive"))
      (node (ref "C12") (pin "1") (pinfunction "1_1") (pintype "passive"))
      (node (ref "C13") (pin "1") (pinfunction "1_1") (pintype "passive"))
      (node (ref "C14") (pin "1") (pinfunction "1_1") (pintype "passive"))
      (node (ref "C15") (pin "2") (pinfunction "2_2") (pintype "passive"))
      (node (ref "C16") (pin "2") (pinfunction "2_2") (pintype "passive"))
      (node (ref "C17") (pin "2") (pinfunction "2_2") (pintype "passive"))
      (node (ref "C18") (pin "1") (pinfunction "1_1") (pintype "passive"))
      (node (ref "C19") (pin "1") (pinfunction "1_1") (pintype "passive"))
      (node (ref "C2") (pin "2") (pinfunction "2_2") (pintype "passive"))
      (node (ref "C25") (pin "2") (pinfunction "2_2") (pintype "passive"))
      (node (ref "C26") (pin "2") (pinfunction "2_2") (pintype "passive"))
      (node (ref "C3") (pin "2") (pinfunction "2_2") (pintype "passive"))
      (node (ref "C33") (pin "1") (pinfunction "1_1") (pintype "passive"))
      (node (ref "C34") (pin "1") (pinfunction "1_1") (pintype "passive"))
      (node (ref "C4") (pin "1") (pinfunction "1_1") (pintype "passive"))
      (node (ref "C5") (pin "2") (pinfunction "2_2") (pintype "passive"))
      (node (ref "C7") (pin "1") (pinfunction "1_1") (pintype "passive"))
      (node (ref "C8") (pin "1") (pinfunction "1_1") (pintype "passive"))
      (node (ref "C9") (pin "1") (pinfunction "1_1") (pintype "passive"))
      (node (ref "CN1") (pin "5") (pinfunction "5_5") (pintype "passive"))
      (node (ref "CN2") (pin "1") (pinfunction "1_1") (pintype "passive"))
      (node (ref "CN5") (pin "1") (pinfunction "1_1") (pintype "passive"))
      (node (ref "D19") (pin "1") (pinfunction "A_1") (pintype "passive"))
      (node (ref "D23") (pin "1") (pinfunction "A_1") (pintype "passive"))
      (node (ref "D3") (pin "1") (pinfunction "A_1") (pintype "passive"))
      (node (ref "D4") (pin "1") (pinfunction "A_1") (pintype "passive"))
      (node (ref "J2") (pin "4") (pinfunction "4_4") (pintype "passive"))
      (node (ref "J3") (pin "4") (pinfunction "4_4") (pintype "passive"))
      (node (ref "MOV1") (pin "2") (pinfunction "2_2") (pintype "passive"))
      (node (ref "Q6") (pin "3") (pinfunction "S_3") (pintype "passive"))
      (node (ref "R25") (pin "1") (pinfunction "1_1") (pintype "passive"))
      (node (ref "R27") (pin "1") (pinfunction "1_1") (pintype "passive"))
      (node (ref "R28") (pin "2") (pinfunction "2_2") (pintype "passive"))
      (node (ref "R29") (pin "1") (pinfunction "1_1") (pintype "passive"))
      (node (ref "R32") (pin "1") (pinfunction "1_1") (pintype "passive"))
      (node (ref "R33") (pin "1") (pinfunction "1_1") (pintype "passive"))
      (node (ref "R35") (pin "1") (pinfunction "1_1") (pintype "passive"))
      (node (ref "R36") (pin "1") (pinfunction "1_1") (pintype "passive"))
      (node (ref "R6") (pin "2") (pinfunction "2_2") (pintype "passive"))
      (node (ref "R8") (pin "1") (pinfunction "1_1") (pintype "passive"))
      (node (ref "RT1") (pin "2") (pinfunction "2_2") (pintype "passive"))
      (node (ref "RT2") (pin "2") (pinfunction "2_2") (pintype "passive"))
      (node (ref "U1") (pin "3") (pinfunction "GND_3") (pintype "passive"))
      (node (ref "U1") (pin "5") (pinfunction "EN_5") (pintype "passive"))
      (node (ref "U2") (pin "2") (pinfunction "GND_2") (pintype "passive"))
      (node (ref "U3") (pin "1") (pinfunction "GND_1") (pintype "passive"))
      (node (ref "U4") (pin "8") (pinfunction "GND_8") (pintype "passive"))
      (node (ref "U7") (pin "33") (pinfunction "EP_33") (pintype "passive"))
      (node (ref "U7") (pin "5") (pinfunction "VSS_5") (pintype "passive"))
    )
    (net (code "55") (name "Net-(D1-K)") (class "Default")
      (node (ref "D1") (pin "2") (pinfunction "K_2") (pintype "passive"))
      (node (ref "LR1") (pin "2") (pinfunction "2_2") (pintype "passive"))
    )
    (net (code "56") (name "Net-(D3-K)") (class "Default")
      (node (ref "D3") (pin "2") (pinfunction "K_2") (pintype "passive"))
      (node (ref "L3") (pin "1") (pinfunction "1_1") (pintype "passive"))
      (node (ref "U1") (pin "2") (pinfunction "OUT_2") (pintype "passive"))
    )
    (net (code "57") (name "Net-(D6-A)") (class "Default")
      (node (ref "D6") (pin "1") (pinfunction "A_1") (pintype "passive"))
      (node (ref "Q1") (pin "1") (pinfunction "G_1") (pintype "passive"))
      (node (ref "R11") (pin "2") (pinfunction "2_2") (pintype "passive"))
      (node (ref "R15") (pin "1") (pinfunction "1_1") (pintype "passive"))
    )
    (net (code "58") (name "Net-(D7-A)") (class "Default")
      (node (ref "D7") (pin "1") (pinfunction "A_1") (pintype "passive"))
      (node (ref "Q2") (pin "1") (pinfunction "G_1") (pintype "passive"))
      (node (ref "R12") (pin "2") (pinfunction "2_2") (pintype "passive"))
      (node (ref "R16") (pin "1") (pinfunction "1_1") (pintype "passive"))
    )
    (net (code "59") (name "Net-(D8-A)") (class "Default")
      (node (ref "D8") (pin "1") (pinfunction "A_1") (pintype "passive"))
      (node (ref "Q3") (pin "1") (pinfunction "G_1") (pintype "passive"))
      (node (ref "R13") (pin "2") (pinfunction "2_2") (pintype "passive"))
      (node (ref "R17") (pin "1") (pinfunction "1_1") (pintype "passive"))
    )
    (net (code "60") (name "Net-(D14-A)") (class "Default")
      (node (ref "D14") (pin "1") (pinfunction "A_1") (pintype "passive"))
      (node (ref "Q4") (pin "1") (pinfunction "G_1") (pintype "passive"))
      (node (ref "R18") (pin "2") (pinfunction "2_2") (pintype "passive"))
      (node (ref "R24") (pin "1") (pinfunction "1_1") (pintype "passive"))
    )
    (net (code "61") (name "Net-(D15-A)") (class "Default")
      (node (ref "D15") (pin "1") (pinfunction "A_1") (pintype "passive"))
      (node (ref "Q5") (pin "1") (pinfunction "G_1") (pintype "passive"))
      (node (ref "R19") (pin "2") (pinfunction "2_2") (pintype "passive"))
      (node (ref "R26") (pin "1") (pinfunction "1_1") (pintype "passive"))
    )
    (net (code "62") (name "Net-(D16-A)") (class "Default")
      (node (ref "D16") (pin "1") (pinfunction "A_1") (pintype "passive"))
      (node (ref "Q6") (pin "1") (pinfunction "G_1") (pintype "passive"))
      (node (ref "R20") (pin "2") (pinfunction "2_2") (pintype "passive"))
      (node (ref "R28") (pin "1") (pinfunction "1_1") (pintype "passive"))
    )
    (net (code "63") (name "Net-(D19-K)") (class "Default")
      (node (ref "D19") (pin "2") (pinfunction "K_2") (pintype "passive"))
      (node (ref "J2") (pin "2") (pinfunction "2_2") (pintype "passive"))
      (node (ref "R41") (pin "2") (pinfunction "2_2") (pintype "passive"))
    )
    (net (code "64") (name "Net-(D23-K)") (class "Default")
      (node (ref "D23") (pin "2") (pinfunction "K_2") (pintype "passive"))
      (node (ref "J2") (pin "3") (pinfunction "3_3") (pintype "passive"))
      (node (ref "R45") (pin "2") (pinfunction "2_2") (pintype "passive"))
    )
    (net (code "65") (name "Net-(Q4-S)") (class "Default")
      (node (ref "Q4") (pin "3") (pinfunction "S_3") (pintype "passive"))
      (node (ref "R24") (pin "2") (pinfunction "2_2") (pintype "passive"))
      (node (ref "R30") (pin "1") (pinfunction "1_1") (pintype "passive"))
      (node (ref "R32") (pin "2") (pinfunction "2_2") (pintype "passive"))
    )
    (net (code "66") (name "Net-(Q5-S)") (class "Default")
      (node (ref "Q5") (pin "3") (pinfunction "S_3") (pintype "passive"))
      (node (ref "R26") (pin "2") (pinfunction "2_2") (pintype "passive"))
      (node (ref "R31") (pin "1") (pinfunction "1_1") (pintype "passive"))
      (node (ref "R33") (pin "2") (pinfunction "2_2") (pintype "passive"))
    )
    (net (code "67") (name "Net-(U2-BS)") (class "Default")
      (node (ref "C1") (pin "1") (pinfunction "1_1") (pintype "passive"))
      (node (ref "U2") (pin "1") (pinfunction "BS_1") (pintype "passive"))
    )
    (net (code "68") (name "Net-(U2-EN)") (class "Default")
      (node (ref "R4") (pin "2") (pinfunction "2_2") (pintype "passive"))
      (node (ref "U2") (pin "4") (pinfunction "EN_4") (pintype "passive"))
    )
    (net (code "69") (name "Net-(U2-FB)") (class "Default")
      (node (ref "C6") (pin "1") (pinfunction "1_1") (pintype "passive"))
      (node (ref "R5") (pin "1") (pinfunction "1_1") (pintype "passive"))
      (node (ref "R8") (pin "2") (pinfunction "2_2") (pintype "passive"))
      (node (ref "U2") (pin "3") (pinfunction "FB_3") (pintype "passive"))
    )
    (net (code "70") (name "Net-(U2-IN)") (class "Default")
      (node (ref "C17") (pin "1") (pinfunction "1_1") (pintype "passive"))
      (node (ref "C18") (pin "2") (pinfunction "2_2") (pintype "passive"))
      (node (ref "LR1") (pin "1") (pinfunction "1_1") (pintype "passive"))
      (node (ref "R4") (pin "1") (pinfunction "1_1") (pintype "passive"))
      (node (ref "U2") (pin "5") (pinfunction "IN_5") (pintype "passive"))
    )
    (net (code "71") (name "Net-(U2-LX)") (class "Default")
      (node (ref "C1") (pin "2") (pinfunction "2_2") (pintype "passive"))
      (node (ref "L2") (pin "1") (pinfunction "1_1") (pintype "passive"))
      (node (ref "U2") (pin "6") (pinfunction "LX_6") (pintype "passive"))
    )
    (net (code "72") (name "V-FILT") (class "Default")
      (node (ref "C12") (pin "2") (pinfunction "2_2") (pintype "passive"))
      (node (ref "C13") (pin "2") (pinfunction "2_2") (pintype "passive"))
      (node (ref "C2") (pin "1") (pinfunction "1_1") (pintype "passive"))
      (node (ref "C3") (pin "1") (pinfunction "1_1") (pintype "passive"))
      (node (ref "L1") (pin "2") (pinfunction "2_2") (pintype "passive"))
      (node (ref "U1") (pin "1") (pinfunction "VIN_1") (pintype "passive"))
    )
    (net (code "73") (name "VCC") (class "Default")
      (node (ref "C11") (pin "2") (pinfunction "2_2") (pintype "passive"))
      (node (ref "C4") (pin "2") (pinfunction "2_2") (pintype "passive"))
      (node (ref "D2") (pin "2") (pinfunction "K_2") (pintype "passive"))
      (node (ref "D4") (pin "2") (pinfunction "K_2") (pintype "passive"))
      (node (ref "L1") (pin "1") (pinfunction "1_1") (pintype "passive"))
    )
  )
)
